# mod_mixer.net
KiCad netlist of a schematic drawn in EAGLE
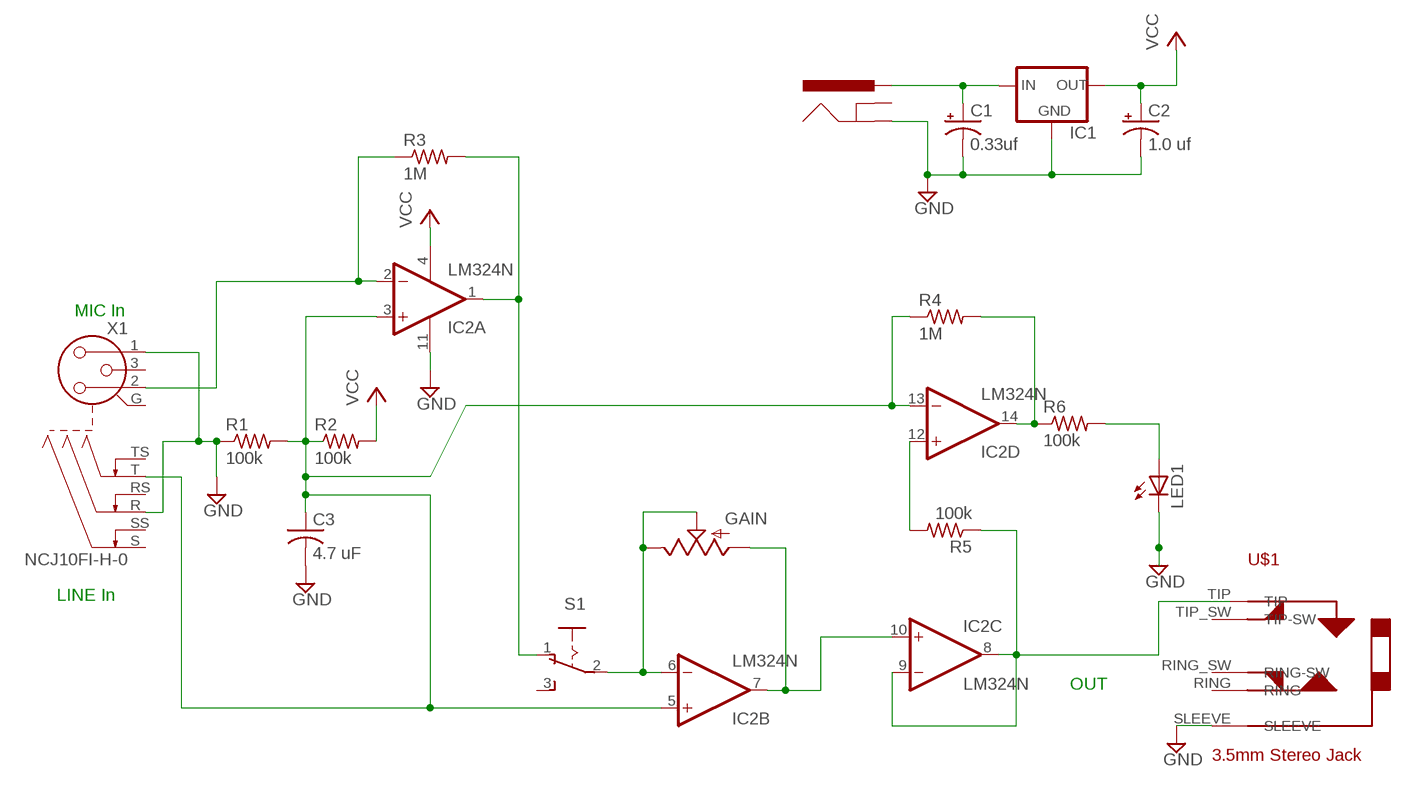
[diagram p0: schematic, sheet 1]

(export (version "E")
  (design (tool "Eeschema 10.0.6"))
  (components
    (comp (ref "C1")
      (value "0.33uf")
      (footprint "eagle-import:E2,5-6")
      (libsource (lib "eagle-import") (part "CPOL-USE2.5-6"))
    )
    (comp (ref "C2")
      (value "1.0 uf")
      (footprint "eagle-import:E2,5-6")
      (libsource (lib "eagle-import") (part "CPOL-USE2.5-6"))
    )
    (comp (ref "C3")
      (value "4.7 uF")
      (footprint "eagle-import:C050-030X075")
      (libsource (lib "eagle-import") (part "C-US050-030X075"))
    )
    (comp (ref "GAIN")
      (value "POT")
      (footprint "eagle-import:ALPS_POT")
      (libsource (lib "eagle-import") (part "POT"))
    )
    (comp (ref "IC1")
      (value "V_REG_78XXSIDE")
      (footprint "eagle-import:78XXL")
      (libsource (lib "eagle-import") (part "V_REG_78XXSIDE"))
    )
    (comp (ref "IC2")
      (value "LM324N")
      (footprint "eagle-import:DIL14")
      (libsource (lib "eagle-import") (part "LM324N"))
    )
    (comp (ref "J1")
      (value "POWER_JACKSLT")
      (footprint "eagle-import:POWER_JACK_SLOT")
      (libsource (lib "eagle-import") (part "POWER_JACKSLT"))
    )
    (comp (ref "LED1")
      (value "LED3MM")
      (footprint "eagle-import:LED3MM")
      (libsource (lib "eagle-import") (part "LED3MM"))
    )
    (comp (ref "R1")
      (value "100k")
      (footprint "eagle-import:0207_10")
      (libsource (lib "eagle-import") (part "R-US_0207/10"))
    )
    (comp (ref "R2")
      (value "100k")
      (footprint "eagle-import:0207_10")
      (libsource (lib "eagle-import") (part "R-US_0207/10"))
    )
    (comp (ref "R3")
      (value "1M")
      (footprint "eagle-import:0207_10")
      (libsource (lib "eagle-import") (part "R-US_0207/10"))
    )
    (comp (ref "R4")
      (value "1M")
      (footprint "eagle-import:0207_10")
      (libsource (lib "eagle-import") (part "R-US_0207/10"))
    )
    (comp (ref "R5")
      (value "100k")
      (footprint "eagle-import:0207_10")
      (libsource (lib "eagle-import") (part "R-US_0207/10"))
    )
    (comp (ref "R6")
      (value "100k")
      (footprint "eagle-import:0207_10")
      (libsource (lib "eagle-import") (part "R-US_0207/10"))
    )
    (comp (ref "S1")
      (value "255SB")
      (footprint "eagle-import:255SB")
      (libsource (lib "eagle-import") (part "255SB"))
    )
    (comp (ref "U$1")
      (value "PICAXE_STEREOJACKSOCKET")
      (footprint "eagle-import:PICAXE_STEREOJACKSOCKET")
      (libsource (lib "eagle-import") (part "PICAXE_STEREOJACKSOCKET"))
    )
    (comp (ref "X1")
      (value "NCJ10FI-H-0")
      (footprint "eagle-import:NCJ10FI-H-0")
      (libsource (lib "eagle-import") (part "NCJ10FI-H-0"))
    )
  )
  (nets
    (net (code "1") (name "GND") (class "Default")
      (node (ref "C1") (pin "-") (pinfunction "-_-") (pintype "passive"))
      (node (ref "C2") (pin "-") (pinfunction "-_-") (pintype "passive"))
      (node (ref "C3") (pin "2") (pinfunction "2_2") (pintype "passive"))
      (node (ref "IC1") (pin "GND") (pinfunction "GND_GND") (pintype "input"))
      (node (ref "IC2") (pin "11") (pinfunction "V-_11") (pintype "power_in"))
      (node (ref "J1") (pin "GND@2") (pinfunction "GND_GND@2") (pintype "bidirectional"))
      (node (ref "LED1") (pin "K") (pinfunction "C_K") (pintype "passive"))
      (node (ref "R1") (pin "1") (pinfunction "1_1") (pintype "passive"))
      (node (ref "U$1") (pin "SLEEVE") (pinfunction "SLEEVE_SLEEVE") (pintype "bidirectional"))
      (node (ref "X1") (pin "1") (pinfunction "1_1") (pintype "passive"))
      (node (ref "X1") (pin "R") (pinfunction "R_R") (pintype "passive"))
    )
    (net (code "2") (name "Net-(C1-Pad+)") (class "Default")
      (node (ref "C1") (pin "+") (pinfunction "+_+") (pintype "passive"))
      (node (ref "IC1") (pin "IN") (pinfunction "IN_IN") (pintype "input"))
      (node (ref "J1") (pin "PWR") (pinfunction "PWR_PWR") (pintype "bidirectional"))
    )
    (net (code "3") (name "Net-(GAIN-A)") (class "Default")
      (node (ref "GAIN") (pin "P$3") (pinfunction "A_P$3") (pintype "passive"))
      (node (ref "IC2") (pin "10") (pinfunction "+IN_10") (pintype "input"))
      (node (ref "IC2") (pin "7") (pinfunction "OUT_7") (pintype "output"))
    )
    (net (code "4") (name "Net-(GAIN-E)") (class "Default")
      (node (ref "GAIN") (pin "P$1") (pinfunction "E_P$1") (pintype "passive"))
      (node (ref "GAIN") (pin "P$2") (pinfunction "S_P$2") (pintype "passive"))
      (node (ref "IC2") (pin "6") (pinfunction "-IN_6") (pintype "input"))
      (node (ref "S1") (pin "2") (pinfunction "P_2") (pintype "passive"))
    )
    (net (code "5") (name "Net-(IC2A-+IN)") (class "Default")
      (node (ref "C3") (pin "1") (pinfunction "1_1") (pintype "passive"))
      (node (ref "IC2") (pin "13") (pinfunction "-IN_13") (pintype "input"))
      (node (ref "IC2") (pin "3") (pinfunction "+IN_3") (pintype "input"))
      (node (ref "IC2") (pin "5") (pinfunction "+IN_5") (pintype "input"))
      (node (ref "R1") (pin "2") (pinfunction "2_2") (pintype "passive"))
      (node (ref "R2") (pin "1") (pinfunction "1_1") (pintype "passive"))
      (node (ref "R4") (pin "1") (pinfunction "1_1") (pintype "passive"))
      (node (ref "X1") (pin "T") (pinfunction "T_T") (pintype "passive"))
    )
    (net (code "6") (name "Net-(IC2A--IN)") (class "Default")
      (node (ref "IC2") (pin "2") (pinfunction "-IN_2") (pintype "input"))
      (node (ref "R3") (pin "1") (pinfunction "1_1") (pintype "passive"))
      (node (ref "X1") (pin "2") (pinfunction "2_2") (pintype "passive"))
    )
    (net (code "7") (name "Net-(IC2A-OUT)") (class "Default")
      (node (ref "IC2") (pin "1") (pinfunction "OUT_1") (pintype "output"))
      (node (ref "R3") (pin "2") (pinfunction "2_2") (pintype "passive"))
      (node (ref "S1") (pin "1") (pinfunction "O_1") (pintype "passive"))
    )
    (net (code "8") (name "Net-(IC2C--IN)") (class "Default")
      (node (ref "IC2") (pin "8") (pinfunction "OUT_8") (pintype "output"))
      (node (ref "IC2") (pin "9") (pinfunction "-IN_9") (pintype "input"))
      (node (ref "R5") (pin "1") (pinfunction "1_1") (pintype "passive"))
    )
    (net (code "9") (name "Net-(IC2D-+IN)") (class "Default")
      (node (ref "IC2") (pin "12") (pinfunction "+IN_12") (pintype "input"))
      (node (ref "R5") (pin "2") (pinfunction "2_2") (pintype "passive"))
    )
    (net (code "10") (name "Net-(IC2D-OUT)") (class "Default")
      (node (ref "IC2") (pin "14") (pinfunction "OUT_14") (pintype "output"))
      (node (ref "R4") (pin "2") (pinfunction "2_2") (pintype "passive"))
      (node (ref "R6") (pin "1") (pinfunction "1_1") (pintype "passive"))
    )
    (net (code "11") (name "Net-(LED1-PadA)") (class "Default")
      (node (ref "LED1") (pin "A") (pinfunction "A_A") (pintype "passive"))
      (node (ref "R6") (pin "2") (pinfunction "2_2") (pintype "passive"))
    )
    (net (code "12") (name "VCC") (class "Default")
      (node (ref "C2") (pin "+") (pinfunction "+_+") (pintype "passive"))
      (node (ref "IC1") (pin "OUT") (pinfunction "OUT_OUT") (pintype "output"))
      (node (ref "IC2") (pin "4") (pinfunction "V+_4") (pintype "power_in"))
      (node (ref "R2") (pin "2") (pinfunction "2_2") (pintype "passive"))
    )
    (net (code "13") (name "unconnected-(J1-GNDBREAK-PadGND@1)") (class "Default")
      (node (ref "J1") (pin "GND@1") (pinfunction "GNDBREAK_GND@1") (pintype "bidirectional"))
    )
    (net (code "14") (name "unconnected-(S1-S-Pad3)") (class "Default")
      (node (ref "S1") (pin "3") (pinfunction "S_3") (pintype "passive"))
    )
    (net (code "15") (name "unconnected-(U$1-PadRING)") (class "Default")
      (node (ref "U$1") (pin "RING") (pinfunction "RING_RING") (pintype "bidirectional"))
    )
    (net (code "16") (name "unconnected-(U$1-PadTIP)") (class "Default")
      (node (ref "U$1") (pin "TIP") (pinfunction "TIP_TIP") (pintype "bidirectional"))
    )
    (net (code "17") (name "unconnected-(U$1-RING-SW-PadRING_SW)") (class "Default")
      (node (ref "U$1") (pin "RING_SW") (pinfunction "RING-SW_RING_SW") (pintype "bidirectional"))
    )
    (net (code "18") (name "unconnected-(U$1-TIP-SW-PadTIP_SW)") (class "Default")
      (node (ref "U$1") (pin "TIP_SW") (pinfunction "TIP-SW_TIP_SW") (pintype "bidirectional"))
    )
    (net (code "19") (name "unconnected-(X1-Pad3)") (class "Default")
      (node (ref "X1") (pin "3") (pinfunction "3_3") (pintype "passive"))
    )
    (net (code "20") (name "unconnected-(X1-PadG)") (class "Default")
      (node (ref "X1") (pin "G") (pinfunction "G_G") (pintype "passive"))
    )
    (net (code "21") (name "unconnected-(X1-PadRS)") (class "Default")
      (node (ref "X1") (pin "RS") (pinfunction "RS_RS") (pintype "passive"))
    )
    (net (code "22") (name "unconnected-(X1-PadS)") (class "Default")
      (node (ref "X1") (pin "S") (pinfunction "S_S") (pintype "passive"))
    )
    (net (code "23") (name "unconnected-(X1-PadSS)") (class "Default")
      (node (ref "X1") (pin "SS") (pinfunction "SS_SS") (pintype "passive"))
    )
    (net (code "24") (name "unconnected-(X1-PadTS)") (class "Default")
      (node (ref "X1") (pin "TS") (pinfunction "TS_TS") (pintype "passive"))
    )
  )
)
